# ETA1090SheetV2.net
KiCad netlist of a schematic drawn in Altium Designer
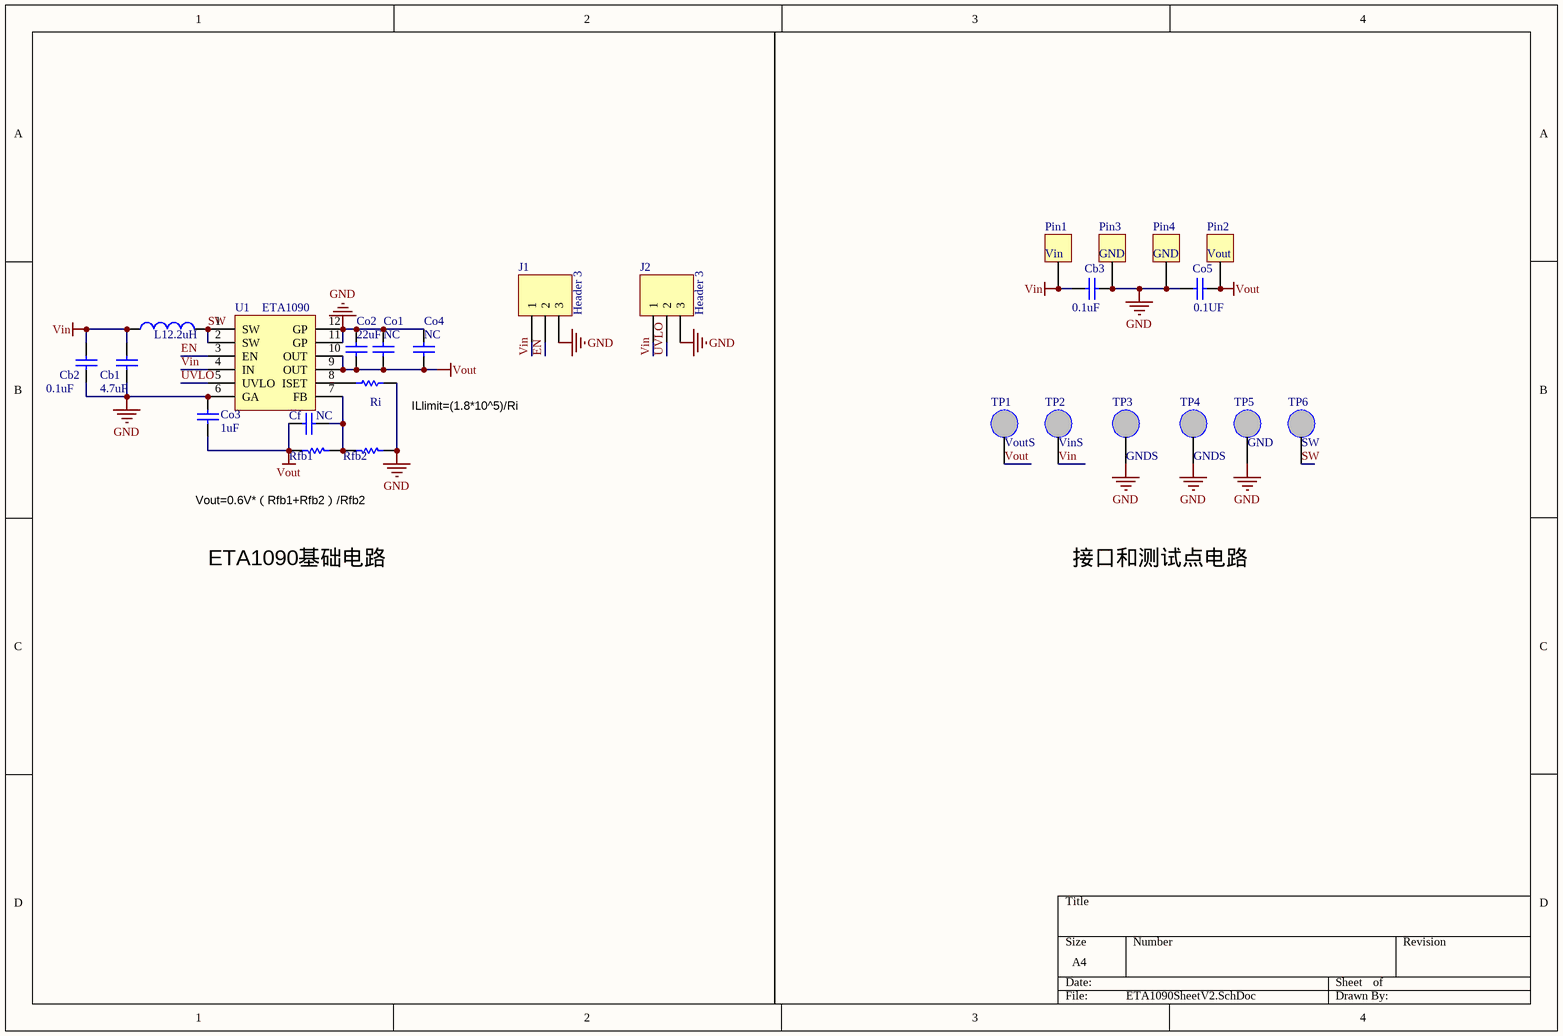
[diagram p0: ETA1090SheetV2.SchDoc]

(export (version "E")
  (design (tool "Eeschema 10.0.6"))
  (components
    (comp (ref "Cb1")
      (value "4.7uF")
      (footprint "C0805")
      (description "Capacitor")
      (fields (field (name "Comment") "Cap") (field (name "PUBLISHER") "Altium Limited"))
      (libsource (lib "Miscellaneous Devices") (part "Cap"))
    )
    (comp (ref "Cb2")
      (value "0.1uF")
      (footprint "C0603")
      (description "Capacitor")
      (fields (field (name "Comment") "Cap") (field (name "PUBLISHER") "Altium Limited"))
      (libsource (lib "Miscellaneous Devices") (part "Cap"))
    )
    (comp (ref "Cb3")
      (value "0.1uF")
      (footprint "C0603")
      (description "Capacitor")
      (fields (field (name "Comment") "Cap") (field (name "PUBLISHER") "Altium Limited"))
      (libsource (lib "Miscellaneous Devices") (part "Cap"))
    )
    (comp (ref "Cf")
      (value "NC")
      (footprint "C0603")
      (description "Capacitor (Semiconductor SIM Model)")
      (fields (field (name "Comment") "Cap Semi") (field (name "PUBLISHER") "Altium Limited"))
      (libsource (lib "Miscellaneous Devices") (part "Cap Semi"))
    )
    (comp (ref "Co1")
      (value "NC")
      (footprint "C0805")
      (description "Capacitor")
      (fields (field (name "Comment") "Cap") (field (name "PUBLISHER") "Altium Limited"))
      (libsource (lib "Miscellaneous Devices") (part "Cap"))
    )
    (comp (ref "Co2")
      (value "22uF")
      (footprint "C0805")
      (description "Capacitor")
      (fields (field (name "PUBLISHER") "Altium Limited"))
      (libsource (lib "Miscellaneous Devices") (part "Cap"))
    )
    (comp (ref "Co3")
      (value "1uF")
      (footprint "C0603")
      (description "Capacitor")
      (fields (field (name "PUBLISHER") "Altium Limited"))
      (libsource (lib "Miscellaneous Devices") (part "Cap"))
    )
    (comp (ref "Co4")
      (value "NC")
      (footprint "C0603")
      (description "Capacitor")
      (fields (field (name "PUBLISHER") "Altium Limited"))
      (libsource (lib "Miscellaneous Devices") (part "Cap"))
    )
    (comp (ref "Co5")
      (value "0.1UF")
      (footprint "C0603")
      (description "Capacitor")
      (fields (field (name "PUBLISHER") "Altium Limited"))
      (libsource (lib "Miscellaneous Devices") (part "Cap"))
    )
    (comp (ref "J1")
      (value "Header 3")
      (footprint "HDR1X3")
      (description "Header, 3-Pin")
      (fields (field (name "PUBLISHER") "Altium Limited"))
      (libsource (lib "Miscellaneous Connectors") (part "Header 3"))
    )
    (comp (ref "J2")
      (value "Header 3")
      (footprint "HDR1X3")
      (description "Header, 3-Pin")
      (fields (field (name "PUBLISHER") "Altium Limited"))
      (libsource (lib "Miscellaneous Connectors") (part "Header 3"))
    )
    (comp (ref "L1")
      (value "2.2uH")
      (footprint "L_8X8")
      (description "Inductor")
      (fields (field (name "PUBLISHER") "Altium Limited"))
      (libsource (lib "Miscellaneous Devices") (part "Inductor"))
    )
    (comp (ref "Pin1")
      (value "Vin")
      (footprint "Ceramic:PIN3")
      (libsource (lib "ETA-LSNSchlib1") (part "TP1"))
    )
    (comp (ref "Pin2")
      (value "Vout")
      (footprint "Ceramic:PIN3")
      (libsource (lib "ETA-LSNSchlib1") (part "TP1"))
    )
    (comp (ref "Pin3")
      (value "GND")
      (footprint "Ceramic:PIN3")
      (libsource (lib "ETA-LSNSchlib1") (part "TP1"))
    )
    (comp (ref "Pin4")
      (value "GND")
      (footprint "Ceramic:PIN3")
      (libsource (lib "ETA-LSNSchlib1") (part "TP1"))
    )
    (comp (ref "Rfb1")
      (value "Res1")
      (footprint "r0603")
      (description "Resistor")
      (fields (field (name "PUBLISHER") "Altium Limited"))
      (libsource (lib "Miscellaneous Devices") (part "Res1"))
    )
    (comp (ref "Rfb2")
      (value "Res1")
      (footprint "r0603")
      (description "Resistor")
      (fields (field (name "PUBLISHER") "Altium Limited"))
      (libsource (lib "Miscellaneous Devices") (part "Res1"))
    )
    (comp (ref "Ri")
      (value "Res1")
      (footprint "r0603")
      (description "Resistor")
      (fields (field (name "PUBLISHER") "Altium Limited"))
      (libsource (lib "Miscellaneous Devices") (part "Res1"))
    )
    (comp (ref "TP1")
      (value "VoutS")
      (footprint "Ceramic:PIN0.8")
      (libsource (lib "ETA-LSNSchlib1") (part "TP2"))
    )
    (comp (ref "TP2")
      (value "VinS")
      (footprint "Ceramic:PIN0.8")
      (libsource (lib "ETA-LSNSchlib1") (part "TP2"))
    )
    (comp (ref "TP3")
      (value "GNDS")
      (footprint "Ceramic:PIN0.8")
      (libsource (lib "ETA-LSNSchlib1") (part "TP2"))
    )
    (comp (ref "TP4")
      (value "GNDS")
      (footprint "Ceramic:PIN0.8")
      (libsource (lib "ETA-LSNSchlib1") (part "TP2"))
    )
    (comp (ref "TP5")
      (value "GND")
      (footprint "Ceramic:PIN0.8")
      (libsource (lib "ETA-LSNSchlib1") (part "TP2"))
    )
    (comp (ref "TP6")
      (value "SW")
      (footprint "Ceramic:PIN0.8")
      (libsource (lib "ETA-LSNSchlib1") (part "TP2"))
    )
    (comp (ref "U1")
      (value "ETA1090")
      (footprint "DFN33_12")
      (description "Header, 6-Pin, Dual row, Right Angle")
      (fields (field (name "PUBLISHER") "Altium Limited"))
      (libsource (lib "PCB_Project1") (part "Header 6X2H"))
    )
  )
  (nets
    (net (code "1") (name "/EN") (class "Default")
      (node (ref "J1") (pin "2") (pinfunction "2_2") (pintype "passive"))
      (node (ref "U1") (pin "3") (pinfunction "EN_3") (pintype "passive"))
    )
    (net (code "2") (name "/SW") (class "Default")
      (node (ref "L1") (pin "1") (pinfunction "1_1") (pintype "passive"))
      (node (ref "TP6") (pin "1") (pinfunction "1_1") (pintype "passive"))
      (node (ref "U1") (pin "1") (pinfunction "SW_1") (pintype "passive"))
      (node (ref "U1") (pin "2") (pinfunction "SW_2") (pintype "passive"))
    )
    (net (code "3") (name "/UVLO") (class "Default")
      (node (ref "J2") (pin "2") (pinfunction "2_2") (pintype "passive"))
      (node (ref "U1") (pin "5") (pinfunction "UVLO_5") (pintype "passive"))
    )
    (net (code "4") (name "GND") (class "Default")
      (node (ref "Cb1") (pin "1") (pinfunction "1_1") (pintype "passive"))
      (node (ref "Cb2") (pin "1") (pinfunction "1_1") (pintype "passive"))
      (node (ref "Cb3") (pin "1") (pinfunction "1_1") (pintype "passive"))
      (node (ref "Co1") (pin "2") (pinfunction "2_2") (pintype "passive"))
      (node (ref "Co2") (pin "2") (pinfunction "2_2") (pintype "passive"))
      (node (ref "Co3") (pin "2") (pinfunction "2_2") (pintype "passive"))
      (node (ref "Co4") (pin "2") (pinfunction "2_2") (pintype "passive"))
      (node (ref "Co5") (pin "2") (pinfunction "2_2") (pintype "passive"))
      (node (ref "J1") (pin "3") (pinfunction "3_3") (pintype "passive"))
      (node (ref "J2") (pin "3") (pinfunction "3_3") (pintype "passive"))
      (node (ref "Pin3") (pin "0") (pinfunction "0_0") (pintype "passive"))
      (node (ref "Pin4") (pin "0") (pinfunction "0_0") (pintype "passive"))
      (node (ref "Rfb2") (pin "1") (pinfunction "1_1") (pintype "passive"))
      (node (ref "Ri") (pin "1") (pinfunction "1_1") (pintype "passive"))
      (node (ref "TP3") (pin "1") (pinfunction "1_1") (pintype "passive"))
      (node (ref "TP4") (pin "1") (pinfunction "1_1") (pintype "passive"))
      (node (ref "TP5") (pin "1") (pinfunction "1_1") (pintype "passive"))
      (node (ref "U1") (pin "11") (pinfunction "GP_11") (pintype "passive"))
      (node (ref "U1") (pin "12") (pinfunction "GP_12") (pintype "passive"))
      (node (ref "U1") (pin "6") (pinfunction "GA_6") (pintype "passive"))
    )
    (net (code "5") (name "Net-(U1-FB)") (class "Default")
      (node (ref "Cf") (pin "1") (pinfunction "1_1") (pintype "passive"))
      (node (ref "Rfb1") (pin "1") (pinfunction "1_1") (pintype "passive"))
      (node (ref "Rfb2") (pin "2") (pinfunction "2_2") (pintype "passive"))
      (node (ref "U1") (pin "7") (pinfunction "FB_7") (pintype "passive"))
    )
    (net (code "6") (name "Net-(U1-ISET)") (class "Default")
      (node (ref "Ri") (pin "2") (pinfunction "2_2") (pintype "passive"))
      (node (ref "U1") (pin "8") (pinfunction "ISET_8") (pintype "passive"))
    )
    (net (code "7") (name "Vin") (class "Default")
      (node (ref "Cb1") (pin "2") (pinfunction "2_2") (pintype "passive"))
      (node (ref "Cb2") (pin "2") (pinfunction "2_2") (pintype "passive"))
      (node (ref "Cb3") (pin "2") (pinfunction "2_2") (pintype "passive"))
      (node (ref "J1") (pin "1") (pinfunction "1_1") (pintype "passive"))
      (node (ref "J2") (pin "1") (pinfunction "1_1") (pintype "passive"))
      (node (ref "L1") (pin "2") (pinfunction "2_2") (pintype "passive"))
      (node (ref "Pin1") (pin "0") (pinfunction "0_0") (pintype "passive"))
      (node (ref "TP2") (pin "1") (pinfunction "1_1") (pintype "passive"))
      (node (ref "U1") (pin "4") (pinfunction "IN_4") (pintype "passive"))
    )
    (net (code "8") (name "Vout") (class "Default")
      (node (ref "Cf") (pin "2") (pinfunction "2_2") (pintype "passive"))
      (node (ref "Co1") (pin "1") (pinfunction "1_1") (pintype "passive"))
      (node (ref "Co2") (pin "1") (pinfunction "1_1") (pintype "passive"))
      (node (ref "Co3") (pin "1") (pinfunction "1_1") (pintype "passive"))
      (node (ref "Co4") (pin "1") (pinfunction "1_1") (pintype "passive"))
      (node (ref "Co5") (pin "1") (pinfunction "1_1") (pintype "passive"))
      (node (ref "Pin2") (pin "0") (pinfunction "0_0") (pintype "passive"))
      (node (ref "Rfb1") (pin "2") (pinfunction "2_2") (pintype "passive"))
      (node (ref "TP1") (pin "1") (pinfunction "1_1") (pintype "passive"))
      (node (ref "U1") (pin "10") (pinfunction "OUT_10") (pintype "passive"))
      (node (ref "U1") (pin "9") (pinfunction "OUT_9") (pintype "passive"))
    )
  )
)
